# Motion_Control_Inputs.net
KiCad netlist of a schematic drawn in Altium Designer
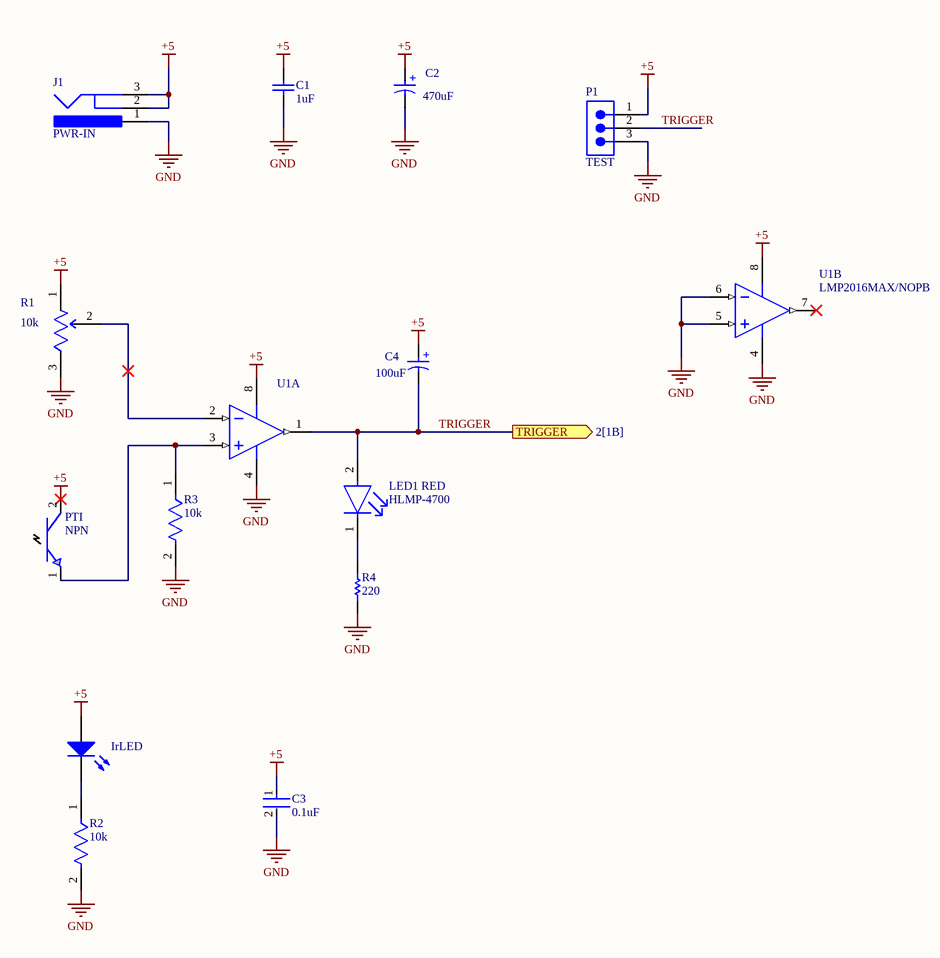
[diagram p0: Motion Control Inputs.SchDoc]

(export (version "E")
  (design (tool "Eeschema 10.0.6"))
  (components
    (comp (ref "C1")
      (value "1uF")
      (footprint "CAPC1206(3216)130_L")
      (description "CAP 1uF 10V ±5% 1206 (3216 Metric) Thickness 1.3mm SMD")
      (fields (field (name "TOLERANCE") "Â±5%"))
      (libsource (lib "MDL") (part "CAP 1uF 10V"))
    )
    (comp (ref "C2")
      (value "470uF")
      (footprint "WCAP-ASLL_D8H10.5")
      (description "WCAP-ASLL Aluminum Electrolytic Capacitors")
      (fields (field (name "TOLERANCE") "20%"))
      (libsource (lib "MDL") (part "CAP POL 470uF 6.3V"))
    )
    (comp (ref "C3")
      (value "0.1uF")
      (footprint "FP-GRM21B-0_1-MFG")
      (description "Chip Multilayer Ceramic Capacitors for General Purpose, 0805, 0.10uF, U2J, -750ppm/°C, 5%, 10V")
      (fields (field (name "TOLERANCE") "5%"))
      (libsource (lib "MDL") (part "CAP 0.1uF 10V 0805"))
    )
    (comp (ref "C4")
      (value "100uF")
      (footprint "WCAP-AS5H_D6.3H5.5")
      (description "WCAP-AS5H Aluminum Electrolytic Capacitors")
      (fields (field (name "TOLERANCE") "20%"))
      (libsource (lib "MDL") (part "CAP POL 100uF 6.3V"))
    )
    (comp (ref "IrLED")
      (value "~")
      (footprint "EVRL-IR333C")
      (description "Infrared LED, 1.2 V, -40 to 85 degC, 2-Pin Radial, RoHS, Bulk")
      (fields (field (name "MANUFACTURER") "Everlight Electronics"))
      (libsource (lib "MDL") (part "IR Emitter 5mm"))
    )
    (comp (ref "J1")
      (value "PWR-IN")
      (footprint "KYCN-KLDX-0202-A_V")
      (description "DC Power Jack, 24 V, 3.5 A, -25 to 85 degC, 3-Pin THD, RoHS")
      (fields (field (name "MANUFACTURER") "Kycon"))
      (libsource (lib "MDL") (part "Conn DC Power Jack 2mm"))
    )
    (comp (ref "LED1 RED")
      (value "HLMP-4700")
      (footprint "FP-HLMP-4700-MFG")
      (description "LED RED DIFFUSED T-1 3/4 T/H")
      (fields
        (field (name "OCTOPART") "https://octopart.com/hlmp-4700-broadcom-71130526")
        (field (name "MANUFACTURER") "Broadcom")
      )
      (libsource (lib "MDL") (part "LED Red 5mm"))
    )
    (comp (ref "P1")
      (value "TEST")
      (footprint "SMTC-TSW-103-07-X-S")
      (description "0.025\" SQ Post Header, Through-hole, Vertical, -55 to 125 degC, 2.54 mm Pitch, 3-Pin, Male, RoHS")
      (fields (field (name "MANUFACTURER") "Samtec") (field (name "PARTNUMBER") "TSW-103-07-F-S"))
      (libsource (lib "MDL") (part "Header 3POS 0.1{dblquote} TH Single Row"))
    )
    (comp (ref "PTI")
      (value "NPN")
      (footprint "PhotoTr_PT3347-6B")
      (description "iber Optic Transceivers; PT334-6B; EVERLIGHT; 2; 940 nm; Through Hole; Yes")
      (fields (field (name "MANUFACTURER") "Everlight") (field (name "MANUFACTURER PART NUMBER") "PT334-6B"))
      (libsource (lib "MDL") (part "Phototransistor"))
    )
    (comp (ref "R1")
      (value "10k")
      (footprint "FP-3296W-MFG")
      (description "TRIMMER 10K OHM 0.5W PC PIN TOP")
      (fields (field (name "TOLERANCE") "10%"))
      (libsource (lib "MDL") (part "10K Trimmer"))
    )
    (comp (ref "R2")
      (value "10k")
      (footprint "FP-CRGCQ1206-IPC_C")
      (description "CRGCQ1206 10KΩ 0.25W 1% ±100ppm/°C 200V")
      (fields (field (name "MANUFACTURER") "TE Connectivity") (field (name "TOLERANCE") "0.01"))
      (libsource (lib "MDL") (part "Res 10K 1/4W SMT"))
    )
    (comp (ref "R3")
      (value "10k")
      (footprint "FP-CRGCQ1206-IPC_C")
      (description "CRGCQ1206 10KΩ 0.25W 1% ±100ppm/°C 200V")
      (fields (field (name "MANUFACTURER") "TE Connectivity") (field (name "TOLERANCE") "0.01"))
      (libsource (lib "MDL") (part "Res 10K 1/4W SMT"))
    )
    (comp (ref "R4")
      (value "220")
      (footprint "RESC3216X60X45ML10T20")
      (fields (field (name "MANUFACTURER") "Vishay Dale") (field (name "PART NUMBER") "CRCW1206220RFKEA"))
      (libsource (lib "MDL") (part "Res 220 Ohm 1/4W SMT"))
    )
    (comp (ref "U1")
      (value "LMP2016MAX/NOPB")
      (footprint "M08A_M")
      (description "High Precision, Rail-to-Rail Output Operational Amplifier, 8-pin Narrow SOIC, Pb-Free")
      (fields (field (name "MANUFACTURER") "National Semiconductor"))
      (libsource (lib "MDL") (part "OPAMP"))
    )
  )
  (nets
    (net (code "1") (name "+5") (class "Default")
      (node (ref "C1") (pin "2") (pinfunction "2_2") (pintype "passive"))
      (node (ref "C2") (pin "1") (pinfunction "P_1") (pintype "passive"))
      (node (ref "C3") (pin "1") (pinfunction "1_1") (pintype "passive"))
      (node (ref "C4") (pin "1") (pinfunction "P_1") (pintype "passive"))
      (node (ref "IrLED") (pin "1") (pinfunction "A_1") (pintype "passive"))
      (node (ref "J1") (pin "2") (pinfunction "2_2") (pintype "passive"))
      (node (ref "J1") (pin "3") (pinfunction "3_3") (pintype "passive"))
      (node (ref "P1") (pin "1") (pinfunction "1_1") (pintype "passive"))
      (node (ref "PTI") (pin "2") (pinfunction "C_2") (pintype "open_collector"))
      (node (ref "R1") (pin "1") (pinfunction "CCW_1") (pintype "passive"))
      (node (ref "U1") (pin "8") (pinfunction "V+_8") (pintype "power_in"))
    )
    (net (code "2") (name "/TRIGGER") (class "Default")
      (node (ref "C4") (pin "2") (pinfunction "N_2") (pintype "passive"))
      (node (ref "LED1 RED") (pin "2") (pinfunction "A_2") (pintype "passive"))
      (node (ref "P1") (pin "2") (pinfunction "2_2") (pintype "passive"))
      (node (ref "U1") (pin "1") (pinfunction "OUT1_1") (pintype "output"))
    )
    (net (code "3") (name "GND") (class "Default")
      (node (ref "C1") (pin "1") (pinfunction "1_1") (pintype "passive"))
      (node (ref "C2") (pin "2") (pinfunction "N_2") (pintype "passive"))
      (node (ref "C3") (pin "2") (pinfunction "2_2") (pintype "passive"))
      (node (ref "J1") (pin "1") (pinfunction "1_1") (pintype "passive"))
      (node (ref "P1") (pin "3") (pinfunction "3_3") (pintype "passive"))
      (node (ref "R1") (pin "3") (pinfunction "CW_3") (pintype "passive"))
      (node (ref "R2") (pin "2") (pinfunction "2_2") (pintype "passive"))
      (node (ref "R3") (pin "2") (pinfunction "2_2") (pintype "passive"))
      (node (ref "R4") (pin "2") (pinfunction "2_2") (pintype "passive"))
      (node (ref "U1") (pin "4") (pinfunction "V-_4") (pintype "power_in"))
      (node (ref "U1") (pin "5") (pinfunction "IN2+_5") (pintype "input"))
      (node (ref "U1") (pin "6") (pinfunction "IN2-_6") (pintype "input"))
    )
    (net (code "4") (name "Net-(IrLED-K)") (class "Default")
      (node (ref "IrLED") (pin "2") (pinfunction "K_2") (pintype "passive"))
      (node (ref "R2") (pin "1") (pinfunction "1_1") (pintype "passive"))
    )
    (net (code "5") (name "Net-(LED1 RED-C)") (class "Default")
      (node (ref "LED1 RED") (pin "1") (pinfunction "C_1") (pintype "passive"))
      (node (ref "R4") (pin "1") (pinfunction "1_1") (pintype "passive"))
    )
    (net (code "6") (name "Net-(PTI-E)") (class "Default")
      (node (ref "PTI") (pin "1") (pinfunction "E_1") (pintype "open_emitter"))
      (node (ref "R3") (pin "1") (pinfunction "1_1") (pintype "passive"))
      (node (ref "U1") (pin "3") (pinfunction "IN1+_3") (pintype "input"))
    )
    (net (code "7") (name "Net-(R1-WIPER)") (class "Default")
      (node (ref "R1") (pin "2") (pinfunction "WIPER_2") (pintype "passive"))
      (node (ref "U1") (pin "2") (pinfunction "IN1-_2") (pintype "input"))
    )
    (net (code "8") (name "unconnected-(U1B-OUT2-Pad7)") (class "Default")
      (node (ref "U1") (pin "7") (pinfunction "OUT2_7") (pintype "output+no_connect"))
    )
  )
)
